# SparkFun_IMU_Breakout_ICM-20948.net
KiCad netlist of a schematic drawn in EAGLE
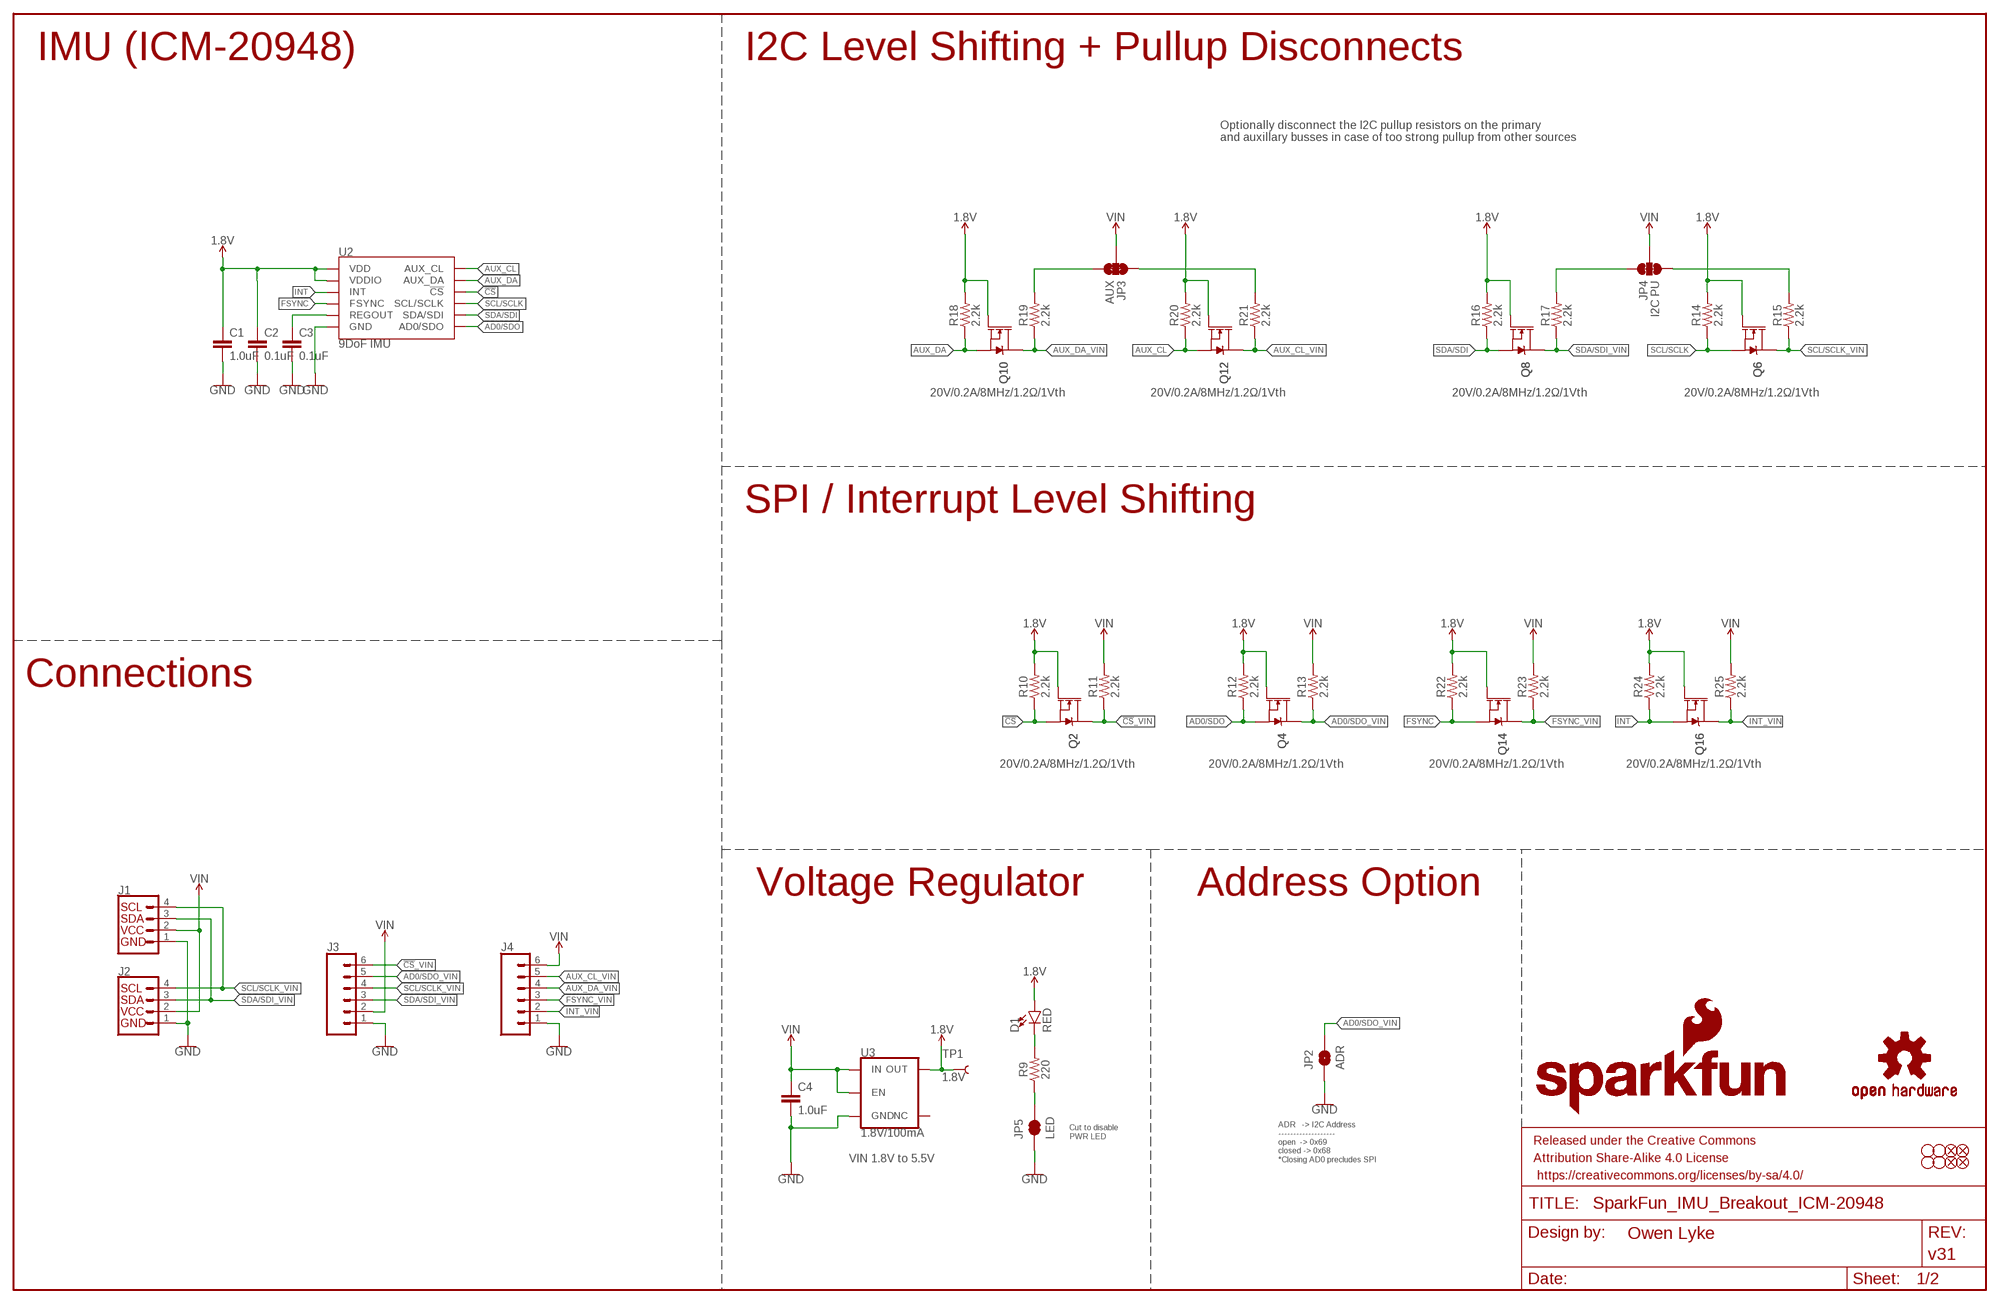
[diagram p0: schematic, sheet 1]
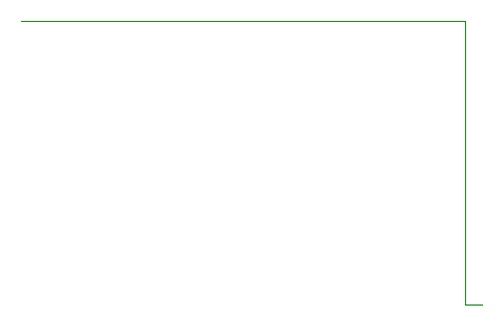
[diagram p1: schematic, sheet 2]

(export (version "E")
  (design (tool "Eeschema 10.0.6"))
  (components
    (comp (ref "C1")
      (value "1.0uF")
      (footprint "eagle-import:0603")
      (libsource (lib "eagle-import") (part "1.0UF-0603-16V-10%-X7R"))
    )
    (comp (ref "C2")
      (value "0.1uF")
      (footprint "eagle-import:0603")
      (libsource (lib "eagle-import") (part "0.1UF-0603-25V-5%"))
    )
    (comp (ref "C3")
      (value "0.1uF")
      (footprint "eagle-import:0603")
      (libsource (lib "eagle-import") (part "0.1UF-0603-25V-5%"))
    )
    (comp (ref "C4")
      (value "1.0uF")
      (footprint "eagle-import:0603")
      (libsource (lib "eagle-import") (part "1.0UF-0603-16V-10%-X7R"))
    )
    (comp (ref "D1")
      (value "RED")
      (footprint "eagle-import:LED-0603")
      (libsource (lib "eagle-import") (part "LED-RED0603"))
    )
    (comp (ref "FD1")
      (value "FIDUCIAL1X2")
      (footprint "eagle-import:FIDUCIAL-1X2")
      (libsource (lib "eagle-import") (part "FIDUCIAL1X2"))
    )
    (comp (ref "FD2")
      (value "FIDUCIAL1X2")
      (footprint "eagle-import:FIDUCIAL-1X2")
      (libsource (lib "eagle-import") (part "FIDUCIAL1X2"))
    )
    (comp (ref "FD3")
      (value "FIDUCIAL1X2")
      (footprint "eagle-import:FIDUCIAL-1X2")
      (libsource (lib "eagle-import") (part "FIDUCIAL1X2"))
    )
    (comp (ref "FD4")
      (value "FIDUCIAL1X2")
      (footprint "eagle-import:FIDUCIAL-1X2")
      (libsource (lib "eagle-import") (part "FIDUCIAL1X2"))
    )
    (comp (ref "FRAME2")
      (value "FRAME-LEDGER")
      (footprint "eagle-import:CREATIVE_COMMONS")
      (fields (field (name "DESIGNER") "Owen Lyke") (field (name "REV") "v31"))
      (libsource (lib "eagle-import") (part "FRAME-LEDGER"))
    )
    (comp (ref "H1")
      (value "STAND-OFF")
      (footprint "eagle-import:STAND-OFF")
      (libsource (lib "eagle-import") (part "STAND-OFF"))
    )
    (comp (ref "H2")
      (value "STAND-OFF")
      (footprint "eagle-import:STAND-OFF")
      (libsource (lib "eagle-import") (part "STAND-OFF"))
    )
    (comp (ref "H3")
      (value "STAND-OFF")
      (footprint "eagle-import:STAND-OFF")
      (libsource (lib "eagle-import") (part "STAND-OFF"))
    )
    (comp (ref "H4")
      (value "STAND-OFF")
      (footprint "eagle-import:STAND-OFF")
      (libsource (lib "eagle-import") (part "STAND-OFF"))
    )
    (comp (ref "J1")
      (value "QWIIC_CONNECTORJS-1MM")
      (footprint "eagle-import:JST04_1MM_RA")
      (libsource (lib "eagle-import") (part "QWIIC_CONNECTORJS-1MM"))
    )
    (comp (ref "J2")
      (value "QWIIC_CONNECTORJS-1MM")
      (footprint "eagle-import:JST04_1MM_RA")
      (libsource (lib "eagle-import") (part "QWIIC_CONNECTORJS-1MM"))
    )
    (comp (ref "J3")
      (value "CONN_06NO_SILK_NO_POP")
      (footprint "eagle-import:1X06_NO_SILK")
      (libsource (lib "eagle-import") (part "CONN_06NO_SILK_NO_POP"))
    )
    (comp (ref "J4")
      (value "CONN_06NO_SILK_NO_POP")
      (footprint "eagle-import:1X06_NO_SILK")
      (libsource (lib "eagle-import") (part "CONN_06NO_SILK_NO_POP"))
    )
    (comp (ref "JP2")
      (value "ADR")
      (footprint "eagle-import:SMT-JUMPER_2_NO_SILK")
      (libsource (lib "eagle-import") (part "JUMPER-SMT_2_NO_SILK"))
    )
    (comp (ref "JP3")
      (value "AUX")
      (footprint "eagle-import:SMT-JUMPER_3_2-NC_TRACE_SILK")
      (libsource (lib "eagle-import") (part "JUMPER-SMT_3_2-NC_TRACE_SILK"))
    )
    (comp (ref "JP4")
      (value "I2C PU")
      (footprint "eagle-import:SMT-JUMPER_3_2-NC_TRACE_SILK")
      (libsource (lib "eagle-import") (part "JUMPER-SMT_3_2-NC_TRACE_SILK"))
    )
    (comp (ref "JP5")
      (value "LED")
      (footprint "eagle-import:SMT-JUMPER_2_NC_TRACE_SILK")
      (libsource (lib "eagle-import") (part "JUMPER-SMT_2_NC_TRACE_SILK"))
    )
    (comp (ref "LOGO1")
      (value "SFE_LOGO_NAME_FLAME.1_INCH")
      (footprint "eagle-import:SFE_LOGO_NAME_FLAME_.1")
      (libsource (lib "eagle-import") (part "SFE_LOGO_NAME_FLAME.1_INCH"))
    )
    (comp (ref "LOGO2")
      (value "OSHW-LOGOMINI")
      (footprint "eagle-import:OSHW-LOGO-MINI")
      (libsource (lib "eagle-import") (part "OSHW-LOGOMINI"))
    )
    (comp (ref "Q2")
      (value "20V/0.2A/8MHz/1.2Ω/1Vth")
      (footprint "eagle-import:SOT-416FL")
      (libsource (lib "eagle-import") (part "MOSFET-NCH-RE1C002UN"))
    )
    (comp (ref "Q4")
      (value "20V/0.2A/8MHz/1.2Ω/1Vth")
      (footprint "eagle-import:SOT-416FL")
      (libsource (lib "eagle-import") (part "MOSFET-NCH-RE1C002UN"))
    )
    (comp (ref "Q6")
      (value "20V/0.2A/8MHz/1.2Ω/1Vth")
      (footprint "eagle-import:SOT-416FL")
      (libsource (lib "eagle-import") (part "MOSFET-NCH-RE1C002UN"))
    )
    (comp (ref "Q8")
      (value "20V/0.2A/8MHz/1.2Ω/1Vth")
      (footprint "eagle-import:SOT-416FL")
      (libsource (lib "eagle-import") (part "MOSFET-NCH-RE1C002UN"))
    )
    (comp (ref "Q10")
      (value "20V/0.2A/8MHz/1.2Ω/1Vth")
      (footprint "eagle-import:SOT-416FL")
      (libsource (lib "eagle-import") (part "MOSFET-NCH-RE1C002UN"))
    )
    (comp (ref "Q12")
      (value "20V/0.2A/8MHz/1.2Ω/1Vth")
      (footprint "eagle-import:SOT-416FL")
      (libsource (lib "eagle-import") (part "MOSFET-NCH-RE1C002UN"))
    )
    (comp (ref "Q14")
      (value "20V/0.2A/8MHz/1.2Ω/1Vth")
      (footprint "eagle-import:SOT-416FL")
      (libsource (lib "eagle-import") (part "MOSFET-NCH-RE1C002UN"))
    )
    (comp (ref "Q16")
      (value "20V/0.2A/8MHz/1.2Ω/1Vth")
      (footprint "eagle-import:SOT-416FL")
      (libsource (lib "eagle-import") (part "MOSFET-NCH-RE1C002UN"))
    )
    (comp (ref "R9")
      (value "220")
      (footprint "eagle-import:0603")
      (libsource (lib "eagle-import") (part "220OHM-0603-1/10W-1%"))
    )
    (comp (ref "R10")
      (value "2.2k")
      (footprint "eagle-import:0402-TIGHT")
      (libsource (lib "eagle-import") (part "2.2KOHM-0402T-1/16W-1%"))
    )
    (comp (ref "R11")
      (value "2.2k")
      (footprint "eagle-import:0402-TIGHT")
      (libsource (lib "eagle-import") (part "2.2KOHM-0402T-1/16W-1%"))
    )
    (comp (ref "R12")
      (value "2.2k")
      (footprint "eagle-import:0402-TIGHT")
      (libsource (lib "eagle-import") (part "2.2KOHM-0402T-1/16W-1%"))
    )
    (comp (ref "R13")
      (value "2.2k")
      (footprint "eagle-import:0402-TIGHT")
      (libsource (lib "eagle-import") (part "2.2KOHM-0402T-1/16W-1%"))
    )
    (comp (ref "R14")
      (value "2.2k")
      (footprint "eagle-import:0402-TIGHT")
      (libsource (lib "eagle-import") (part "2.2KOHM-0402T-1/16W-1%"))
    )
    (comp (ref "R15")
      (value "2.2k")
      (footprint "eagle-import:0402-TIGHT")
      (libsource (lib "eagle-import") (part "2.2KOHM-0402T-1/16W-1%"))
    )
    (comp (ref "R16")
      (value "2.2k")
      (footprint "eagle-import:0402-TIGHT")
      (libsource (lib "eagle-import") (part "2.2KOHM-0402T-1/16W-1%"))
    )
    (comp (ref "R17")
      (value "2.2k")
      (footprint "eagle-import:0402-TIGHT")
      (libsource (lib "eagle-import") (part "2.2KOHM-0402T-1/16W-1%"))
    )
    (comp (ref "R18")
      (value "2.2k")
      (footprint "eagle-import:0402-TIGHT")
      (libsource (lib "eagle-import") (part "2.2KOHM-0402T-1/16W-1%"))
    )
    (comp (ref "R19")
      (value "2.2k")
      (footprint "eagle-import:0402-TIGHT")
      (libsource (lib "eagle-import") (part "2.2KOHM-0402T-1/16W-1%"))
    )
    (comp (ref "R20")
      (value "2.2k")
      (footprint "eagle-import:0402-TIGHT")
      (libsource (lib "eagle-import") (part "2.2KOHM-0402T-1/16W-1%"))
    )
    (comp (ref "R21")
      (value "2.2k")
      (footprint "eagle-import:0402-TIGHT")
      (libsource (lib "eagle-import") (part "2.2KOHM-0402T-1/16W-1%"))
    )
    (comp (ref "R22")
      (value "2.2k")
      (footprint "eagle-import:0402-TIGHT")
      (libsource (lib "eagle-import") (part "2.2KOHM-0402T-1/16W-1%"))
    )
    (comp (ref "R23")
      (value "2.2k")
      (footprint "eagle-import:0402-TIGHT")
      (libsource (lib "eagle-import") (part "2.2KOHM-0402T-1/16W-1%"))
    )
    (comp (ref "R24")
      (value "2.2k")
      (footprint "eagle-import:0402-TIGHT")
      (libsource (lib "eagle-import") (part "2.2KOHM-0402T-1/16W-1%"))
    )
    (comp (ref "R25")
      (value "2.2k")
      (footprint "eagle-import:0402-TIGHT")
      (libsource (lib "eagle-import") (part "2.2KOHM-0402T-1/16W-1%"))
    )
    (comp (ref "TP1")
      (value "1.8V")
      (footprint "eagle-import:PAD.03X.03")
      (libsource (lib "eagle-import") (part "TEST-POINT3"))
    )
    (comp (ref "U2")
      (value "9DoF IMU")
      (footprint "eagle-import:QFN24-3X3")
      (libsource (lib "eagle-import") (part "ICM-20948"))
    )
    (comp (ref "U3")
      (value "1.8V/100mA")
      (footprint "eagle-import:SC70")
      (libsource (lib "eagle-import") (part "V_REG_SP6214-1.8V"))
    )
  )
  (nets
    (net (code "1") (name "1.8V") (class "Default")
      (node (ref "C1") (pin "1") (pinfunction "1_1") (pintype "passive"))
      (node (ref "C2") (pin "1") (pinfunction "1_1") (pintype "passive"))
      (node (ref "D1") (pin "A") (pinfunction "A_A") (pintype "passive"))
      (node (ref "Q10") (pin "1") (pinfunction "G_1") (pintype "bidirectional"))
      (node (ref "Q12") (pin "1") (pinfunction "G_1") (pintype "bidirectional"))
      (node (ref "Q14") (pin "1") (pinfunction "G_1") (pintype "bidirectional"))
      (node (ref "Q16") (pin "1") (pinfunction "G_1") (pintype "bidirectional"))
      (node (ref "Q2") (pin "1") (pinfunction "G_1") (pintype "bidirectional"))
      (node (ref "Q4") (pin "1") (pinfunction "G_1") (pintype "bidirectional"))
      (node (ref "Q6") (pin "1") (pinfunction "G_1") (pintype "bidirectional"))
      (node (ref "Q8") (pin "1") (pinfunction "G_1") (pintype "bidirectional"))
      (node (ref "R10") (pin "2") (pinfunction "2_2") (pintype "passive"))
      (node (ref "R12") (pin "2") (pinfunction "2_2") (pintype "passive"))
      (node (ref "R14") (pin "2") (pinfunction "2_2") (pintype "passive"))
      (node (ref "R16") (pin "2") (pinfunction "2_2") (pintype "passive"))
      (node (ref "R18") (pin "2") (pinfunction "2_2") (pintype "passive"))
      (node (ref "R20") (pin "2") (pinfunction "2_2") (pintype "passive"))
      (node (ref "R22") (pin "2") (pinfunction "2_2") (pintype "passive"))
      (node (ref "R24") (pin "2") (pinfunction "2_2") (pintype "passive"))
      (node (ref "TP1") (pin "P$1") (pinfunction "1_P$1") (pintype "bidirectional"))
      (node (ref "U2") (pin "13") (pinfunction "VDD_13") (pintype "bidirectional"))
      (node (ref "U2") (pin "8") (pinfunction "VDDIO_8") (pintype "bidirectional"))
      (node (ref "U3") (pin "5") (pinfunction "OUT_5") (pintype "passive"))
    )
    (net (code "2") (name "AD0{slash}SDO") (class "Default")
      (node (ref "Q4") (pin "2") (pinfunction "S_2") (pintype "bidirectional"))
      (node (ref "R12") (pin "1") (pinfunction "1_1") (pintype "passive"))
      (node (ref "U2") (pin "9") (pinfunction "AD0/SDO_9") (pintype "bidirectional"))
    )
    (net (code "3") (name "AD0{slash}SDO_VIN") (class "Default")
      (node (ref "J3") (pin "5") (pinfunction "5_5") (pintype "passive"))
      (node (ref "JP2") (pin "2") (pinfunction "2_2") (pintype "passive"))
      (node (ref "Q4") (pin "3") (pinfunction "D_3") (pintype "bidirectional"))
      (node (ref "R13") (pin "1") (pinfunction "1_1") (pintype "passive"))
    )
    (net (code "4") (name "AUX_CL") (class "Default")
      (node (ref "Q12") (pin "2") (pinfunction "S_2") (pintype "bidirectional"))
      (node (ref "R20") (pin "1") (pinfunction "1_1") (pintype "passive"))
      (node (ref "U2") (pin "7") (pinfunction "AUX_CL_7") (pintype "bidirectional"))
    )
    (net (code "5") (name "AUX_CL_VIN") (class "Default")
      (node (ref "J4") (pin "5") (pinfunction "5_5") (pintype "passive"))
      (node (ref "Q12") (pin "3") (pinfunction "D_3") (pintype "bidirectional"))
      (node (ref "R21") (pin "1") (pinfunction "1_1") (pintype "passive"))
    )
    (net (code "6") (name "AUX_DA") (class "Default")
      (node (ref "Q10") (pin "2") (pinfunction "S_2") (pintype "bidirectional"))
      (node (ref "R18") (pin "1") (pinfunction "1_1") (pintype "passive"))
      (node (ref "U2") (pin "21") (pinfunction "AUX_DA_21") (pintype "bidirectional"))
    )
    (net (code "7") (name "AUX_DA_VIN") (class "Default")
      (node (ref "J4") (pin "4") (pinfunction "4_4") (pintype "passive"))
      (node (ref "Q10") (pin "3") (pinfunction "D_3") (pintype "bidirectional"))
      (node (ref "R19") (pin "1") (pinfunction "1_1") (pintype "passive"))
    )
    (net (code "8") (name "FSYNC") (class "Default")
      (node (ref "Q14") (pin "2") (pinfunction "S_2") (pintype "bidirectional"))
      (node (ref "R22") (pin "1") (pinfunction "1_1") (pintype "passive"))
      (node (ref "U2") (pin "11") (pinfunction "FSYNC_11") (pintype "bidirectional"))
    )
    (net (code "9") (name "FSYNC_VIN") (class "Default")
      (node (ref "J4") (pin "3") (pinfunction "3_3") (pintype "passive"))
      (node (ref "Q14") (pin "3") (pinfunction "D_3") (pintype "bidirectional"))
      (node (ref "R23") (pin "1") (pinfunction "1_1") (pintype "passive"))
    )
    (net (code "10") (name "GND") (class "Default")
      (node (ref "C1") (pin "2") (pinfunction "2_2") (pintype "passive"))
      (node (ref "C2") (pin "2") (pinfunction "2_2") (pintype "passive"))
      (node (ref "C3") (pin "2") (pinfunction "2_2") (pintype "passive"))
      (node (ref "C4") (pin "2") (pinfunction "2_2") (pintype "passive"))
      (node (ref "J1") (pin "1") (pinfunction "1_1") (pintype "power_in"))
      (node (ref "J2") (pin "1") (pinfunction "1_1") (pintype "power_in"))
      (node (ref "J3") (pin "1") (pinfunction "1_1") (pintype "passive"))
      (node (ref "J4") (pin "1") (pinfunction "1_1") (pintype "passive"))
      (node (ref "JP2") (pin "1") (pinfunction "1_1") (pintype "passive"))
      (node (ref "JP5") (pin "1") (pinfunction "1_1") (pintype "passive"))
      (node (ref "U2") (pin "18") (pinfunction "GND_18") (pintype "bidirectional"))
      (node (ref "U2") (pin "20") (pinfunction "GND_20") (pintype "bidirectional"))
      (node (ref "U3") (pin "2") (pinfunction "GND_2") (pintype "input"))
    )
    (net (code "11") (name "INT") (class "Default")
      (node (ref "Q16") (pin "2") (pinfunction "S_2") (pintype "bidirectional"))
      (node (ref "R24") (pin "1") (pinfunction "1_1") (pintype "passive"))
      (node (ref "U2") (pin "12") (pinfunction "INT_12") (pintype "bidirectional"))
    )
    (net (code "12") (name "INT_VIN") (class "Default")
      (node (ref "J4") (pin "2") (pinfunction "2_2") (pintype "passive"))
      (node (ref "Q16") (pin "3") (pinfunction "D_3") (pintype "bidirectional"))
      (node (ref "R25") (pin "1") (pinfunction "1_1") (pintype "passive"))
    )
    (net (code "13") (name "Net-(D1-PadC)") (class "Default")
      (node (ref "D1") (pin "C") (pinfunction "C_C") (pintype "passive"))
      (node (ref "R9") (pin "2") (pinfunction "2_2") (pintype "passive"))
    )
    (net (code "14") (name "Net-(JP3-Pad1)") (class "Default")
      (node (ref "JP3") (pin "1") (pinfunction "1_1") (pintype "passive"))
      (node (ref "R21") (pin "2") (pinfunction "2_2") (pintype "passive"))
    )
    (net (code "15") (name "Net-(JP3-Pad3)") (class "Default")
      (node (ref "JP3") (pin "3") (pinfunction "3_3") (pintype "passive"))
      (node (ref "R19") (pin "2") (pinfunction "2_2") (pintype "passive"))
    )
    (net (code "16") (name "Net-(JP4-Pad1)") (class "Default")
      (node (ref "JP4") (pin "1") (pinfunction "1_1") (pintype "passive"))
      (node (ref "R17") (pin "2") (pinfunction "2_2") (pintype "passive"))
    )
    (net (code "17") (name "Net-(JP4-Pad3)") (class "Default")
      (node (ref "JP4") (pin "3") (pinfunction "3_3") (pintype "passive"))
      (node (ref "R15") (pin "2") (pinfunction "2_2") (pintype "passive"))
    )
    (net (code "18") (name "Net-(JP5-Pad2)") (class "Default")
      (node (ref "JP5") (pin "2") (pinfunction "2_2") (pintype "passive"))
      (node (ref "R9") (pin "1") (pinfunction "1_1") (pintype "passive"))
    )
    (net (code "19") (name "Net-(U2-REGOUT)") (class "Default")
      (node (ref "C3") (pin "1") (pinfunction "1_1") (pintype "passive"))
      (node (ref "U2") (pin "10") (pinfunction "REGOUT_10") (pintype "bidirectional"))
    )
    (net (code "20") (name "SCL{slash}SCLK") (class "Default")
      (node (ref "Q6") (pin "2") (pinfunction "S_2") (pintype "bidirectional"))
      (node (ref "R14") (pin "1") (pinfunction "1_1") (pintype "passive"))
      (node (ref "U2") (pin "23") (pinfunction "SCL/SCLK_23") (pintype "bidirectional"))
    )
    (net (code "21") (name "SCL{slash}SCLK_VIN") (class "Default")
      (node (ref "J1") (pin "4") (pinfunction "4_4") (pintype "passive"))
      (node (ref "J2") (pin "4") (pinfunction "4_4") (pintype "passive"))
      (node (ref "J3") (pin "4") (pinfunction "4_4") (pintype "passive"))
      (node (ref "Q6") (pin "3") (pinfunction "D_3") (pintype "bidirectional"))
      (node (ref "R15") (pin "1") (pinfunction "1_1") (pintype "passive"))
    )
    (net (code "22") (name "SDA{slash}SDI") (class "Default")
      (node (ref "Q8") (pin "2") (pinfunction "S_2") (pintype "bidirectional"))
      (node (ref "R16") (pin "1") (pinfunction "1_1") (pintype "passive"))
      (node (ref "U2") (pin "24") (pinfunction "SDA/SDI_24") (pintype "bidirectional"))
    )
    (net (code "23") (name "SDA{slash}SDI_VIN") (class "Default")
      (node (ref "J1") (pin "3") (pinfunction "3_3") (pintype "passive"))
      (node (ref "J2") (pin "3") (pinfunction "3_3") (pintype "passive"))
      (node (ref "J3") (pin "3") (pinfunction "3_3") (pintype "passive"))
      (node (ref "Q8") (pin "3") (pinfunction "D_3") (pintype "bidirectional"))
      (node (ref "R17") (pin "1") (pinfunction "1_1") (pintype "passive"))
    )
    (net (code "24") (name "VIN") (class "Default")
      (node (ref "C4") (pin "1") (pinfunction "1_1") (pintype "passive"))
      (node (ref "J1") (pin "2") (pinfunction "2_2") (pintype "power_in"))
      (node (ref "J2") (pin "2") (pinfunction "2_2") (pintype "power_in"))
      (node (ref "J3") (pin "2") (pinfunction "2_2") (pintype "passive"))
      (node (ref "J4") (pin "6") (pinfunction "6_6") (pintype "passive"))
      (node (ref "JP3") (pin "2") (pinfunction "2_2") (pintype "passive"))
      (node (ref "JP4") (pin "2") (pinfunction "2_2") (pintype "passive"))
      (node (ref "R11") (pin "2") (pinfunction "2_2") (pintype "passive"))
      (node (ref "R13") (pin "2") (pinfunction "2_2") (pintype "passive"))
      (node (ref "R23") (pin "2") (pinfunction "2_2") (pintype "passive"))
      (node (ref "R25") (pin "2") (pinfunction "2_2") (pintype "passive"))
      (node (ref "U3") (pin "1") (pinfunction "IN_1") (pintype "input"))
      (node (ref "U3") (pin "3") (pinfunction "EN_3") (pintype "input"))
    )
    (net (code "25") (name "unconnected-(U3-NC-Pad4)") (class "Default")
      (node (ref "U3") (pin "4") (pinfunction "NC_4") (pintype "no_connect"))
    )
    (net (code "26") (name "~{CS}") (class "Default")
      (node (ref "Q2") (pin "2") (pinfunction "S_2") (pintype "bidirectional"))
      (node (ref "R10") (pin "1") (pinfunction "1_1") (pintype "passive"))
      (node (ref "U2") (pin "22") (pinfunction "~{CS}_22") (pintype "bidirectional"))
    )
    (net (code "27") (name "~{CS}_VIN") (class "Default")
      (node (ref "J3") (pin "6") (pinfunction "6_6") (pintype "passive"))
      (node (ref "Q2") (pin "3") (pinfunction "D_3") (pintype "bidirectional"))
      (node (ref "R11") (pin "1") (pinfunction "1_1") (pintype "passive"))
    )
  )
)
